# Jammer.net
KiCad netlist of a schematic drawn in Altium Designer
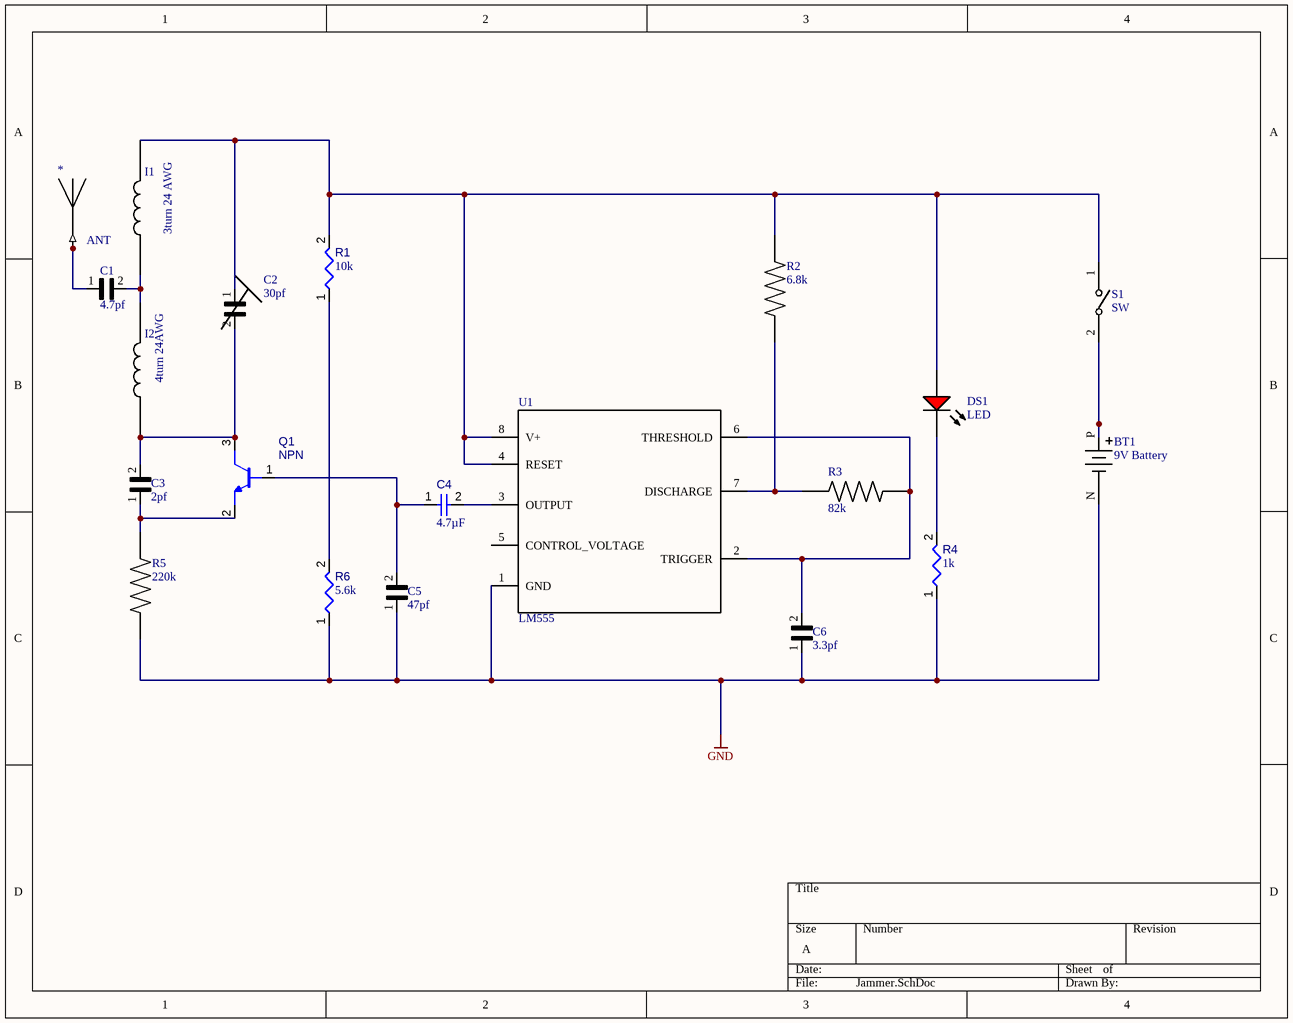
[diagram p0: Jammer.SchDoc]

(export (version "E")
  (design (tool "Eeschema 10.0.6"))
  (components
    (comp (ref "*") (value "ANT") (footprint "ANT") (libsource (lib "Jammer") (part "ANT")))
    (comp (ref "BT1")
      (value "9V Battery")
      (footprint "9V Battery")
      (libsource (lib "Jammer") (part "9V Battery"))
    )
    (comp (ref "C1") (value "4.7pf") (footprint "4.7pf CAP") (libsource (lib "Jammer") (part "4.7pf CAP")))
    (comp (ref "C2")
      (value "30pf")
      (footprint "30pf Trimmer")
      (libsource (lib "Jammer") (part "30pf Trimmer"))
    )
    (comp (ref "C3") (value "2pf") (footprint "2pf CAP") (libsource (lib "Jammer") (part "2pf CAP")))
    (comp (ref "C4")
      (value "4.7µF")
      (footprint "CAPC0805(2012)145_L")
      (description "Chip Capacitor, 4.7µF +/-40%, 25V, 0805, Thickness 1.45 mm")
      (fields (field (name "TOLERANCE") "20%") (field (name "Comment") "Capacitor 4.7µF +/-40% 25V 0805"))
      (libsource (lib "Narendran") (part "CAP-NP-2"))
    )
    (comp (ref "C5") (value "47pf") (footprint "47pf CAP") (libsource (lib "Jammer") (part "47pf CAP")))
    (comp (ref "C6") (value "3.3pf") (footprint "3.3pf CAP") (libsource (lib "Jammer") (part "3.3pf CAP")))
    (comp (ref "DS1")
      (value "LED")
      (footprint "AVAG-HSMX-C190_V")
      (description "LED Uni-Color Red, 65 mW, 20 mA, -40 to 85 degC, 2-Pin SMD, RoHS, Tape and Reel")
      (fields (field (name "POWER") "78mW") (field (name "MANUFACTURER") "Avago"))
      (libsource (lib "Narendran") (part "LED-RED-AK-2"))
    )
    (comp (ref "I1")
      (value "3turn 24 AWG")
      (footprint "Inductor")
      (libsource (lib "Jammer") (part "Inductor"))
    )
    (comp (ref "I2")
      (value "4turn 24AWG")
      (footprint "Inductor")
      (libsource (lib "Jammer") (part "Inductor"))
    )
    (comp (ref "Q1")
      (value "NPN")
      (footprint "ROHM-SOT723-3_V")
      (description "NPN General Purpose Transistor, 3-Pin SOT-723, Pb-Free, Tape and Reel")
      (libsource (lib "Narendran") (part "CMP-00026-6"))
    )
    (comp (ref "R1")
      (value "10k")
      (footprint "RESC1608X55X25ML10T15")
      (description "Chip Resistor, 10 KOhm, +/- 1%, 01 W, -55 to 155 degC, 0603 (1608 Metric)")
      (fields (field (name "POWER") "100mW") (field (name "TOLERANCE") "1%"))
      (libsource (lib "Narendran") (part "RES-2"))
    )
    (comp (ref "R2") (value "6.8k") (footprint "6.8K RES") (libsource (lib "Jammer") (part "6.8K RES")))
    (comp (ref "R3") (value "82k") (footprint "82K RES") (libsource (lib "Jammer") (part "82K RES")))
    (comp (ref "R4")
      (value "1k")
      (footprint "RESC0805(2012)_L")
      (description "Chip Resistor, 1 kOhms, +/-5%, 125 mW, -55 to 155 degC, 0805")
      (fields (field (name "TOLERANCE") "5%") (field (name "POWER") "125mW"))
      (libsource (lib "Narendran") (part "RES-2"))
    )
    (comp (ref "R5") (value "220k") (footprint "220 RES") (libsource (lib "Jammer") (part "220 RES")))
    (comp (ref "R6")
      (value "5.6k")
      (footprint "RESC0402(1005)_L")
      (description "5K6 0.063W 5% 0402 (1005 Metric)  SMD")
      (fields (field (name "TOLERANCE") "5%") (field (name "POWER") "63mW"))
      (libsource (lib "Narendran") (part "5D6KR2J"))
    )
    (comp (ref "S1") (value "SW") (footprint "Switch") (libsource (lib "Jammer") (part "Switch")))
    (comp (ref "U1") (value "LM555") (footprint "LM555") (libsource (lib "Jammer") (part "LM555")))
  )
  (nets
    (net (code "1") (name "GND") (class "Default")
      (node (ref "BT1") (pin "N") (pinfunction "NEG_N") (pintype "passive"))
      (node (ref "C5") (pin "1") (pinfunction "1_1") (pintype "passive"))
      (node (ref "C6") (pin "1") (pinfunction "1_1") (pintype "passive"))
      (node (ref "R4") (pin "1") (pinfunction "1_1") (pintype "passive"))
      (node (ref "R5") (pin "1") (pinfunction "1_1") (pintype "passive"))
      (node (ref "R6") (pin "1") (pinfunction "1_1") (pintype "passive"))
      (node (ref "U1") (pin "1") (pinfunction "GND_1") (pintype "power_in"))
    )
    (net (code "2") (name "Net-(*-FEED-Pad1)") (class "Default")
      (node (ref "*") (pin "1") (pinfunction "FEED_1") (pintype "input"))
      (node (ref "*") (pin "2") (pinfunction "FEED_2") (pintype "input"))
      (node (ref "C1") (pin "1") (pinfunction "1_1") (pintype "passive"))
    )
    (net (code "3") (name "Net-(BT1-POS)") (class "Default")
      (node (ref "BT1") (pin "P") (pinfunction "POS_P") (pintype "passive"))
      (node (ref "S1") (pin "2") (pinfunction "2_2") (pintype "passive"))
    )
    (net (code "4") (name "Net-(C1-Pad2)") (class "Default")
      (node (ref "C1") (pin "2") (pinfunction "2_2") (pintype "passive"))
      (node (ref "I1") (pin "1") (pinfunction "1_1") (pintype "passive"))
      (node (ref "I2") (pin "2") (pinfunction "2_2") (pintype "passive"))
    )
    (net (code "5") (name "Net-(DS1-A)") (class "Default")
      (node (ref "C2") (pin "1") (pinfunction "1_1") (pintype "passive"))
      (node (ref "DS1") (pin "1") (pinfunction "A_1") (pintype "passive"))
      (node (ref "I1") (pin "2") (pinfunction "2_2") (pintype "passive"))
      (node (ref "R1") (pin "2") (pinfunction "2_2") (pintype "passive"))
      (node (ref "R2") (pin "2") (pinfunction "2_2") (pintype "passive"))
      (node (ref "S1") (pin "1") (pinfunction "1_1") (pintype "passive"))
      (node (ref "U1") (pin "4") (pinfunction "RESET_4") (pintype "passive"))
      (node (ref "U1") (pin "8") (pinfunction "V+_8") (pintype "power_in"))
    )
    (net (code "6") (name "Net-(DS1-K)") (class "Default")
      (node (ref "DS1") (pin "2") (pinfunction "K_2") (pintype "passive"))
      (node (ref "R4") (pin "2") (pinfunction "2_2") (pintype "passive"))
    )
    (net (code "7") (name "Net-(Q1-B)") (class "Default")
      (node (ref "C4") (pin "1") (pinfunction "1_1") (pintype "passive"))
      (node (ref "C5") (pin "2") (pinfunction "2_2") (pintype "passive"))
      (node (ref "Q1") (pin "1") (pinfunction "B_1") (pintype "passive"))
    )
    (net (code "8") (name "Net-(Q1-C)") (class "Default")
      (node (ref "C2") (pin "2") (pinfunction "2_2") (pintype "passive"))
      (node (ref "C3") (pin "2") (pinfunction "2_2") (pintype "passive"))
      (node (ref "I2") (pin "1") (pinfunction "1_1") (pintype "passive"))
      (node (ref "Q1") (pin "3") (pinfunction "C_3") (pintype "passive"))
    )
    (net (code "9") (name "Net-(Q1-E)") (class "Default")
      (node (ref "C3") (pin "1") (pinfunction "1_1") (pintype "passive"))
      (node (ref "Q1") (pin "2") (pinfunction "E_2") (pintype "passive"))
      (node (ref "R5") (pin "2") (pinfunction "2_2") (pintype "passive"))
    )
    (net (code "10") (name "Net-(R1-Pad1)") (class "Default")
      (node (ref "R1") (pin "1") (pinfunction "1_1") (pintype "passive"))
      (node (ref "R6") (pin "2") (pinfunction "2_2") (pintype "passive"))
    )
    (net (code "11") (name "Net-(U1-DISCHARGE)") (class "Default")
      (node (ref "R2") (pin "1") (pinfunction "1_1") (pintype "passive"))
      (node (ref "R3") (pin "1") (pinfunction "1_1") (pintype "passive"))
      (node (ref "U1") (pin "7") (pinfunction "DISCHARGE_7") (pintype "passive"))
    )
    (net (code "12") (name "Net-(U1-OUTPUT)") (class "Default")
      (node (ref "C4") (pin "2") (pinfunction "2_2") (pintype "passive"))
      (node (ref "U1") (pin "3") (pinfunction "OUTPUT_3") (pintype "passive"))
    )
    (net (code "13") (name "Net-(U1-THRESHOLD)") (class "Default")
      (node (ref "C6") (pin "2") (pinfunction "2_2") (pintype "passive"))
      (node (ref "R3") (pin "2") (pinfunction "2_2") (pintype "passive"))
      (node (ref "U1") (pin "2") (pinfunction "TRIGGER_2") (pintype "passive"))
      (node (ref "U1") (pin "6") (pinfunction "THRESHOLD_6") (pintype "passive"))
    )
    (net (code "14") (name "unconnected-(U1-CONTROL_VOLTAGE-Pad5)") (class "Default")
      (node (ref "U1") (pin "5") (pinfunction "CONTROL_VOLTAGE_5") (pintype "passive"))
    )
  )
)
